# cpu.net
KiCad netlist of a schematic drawn in Altium Designer
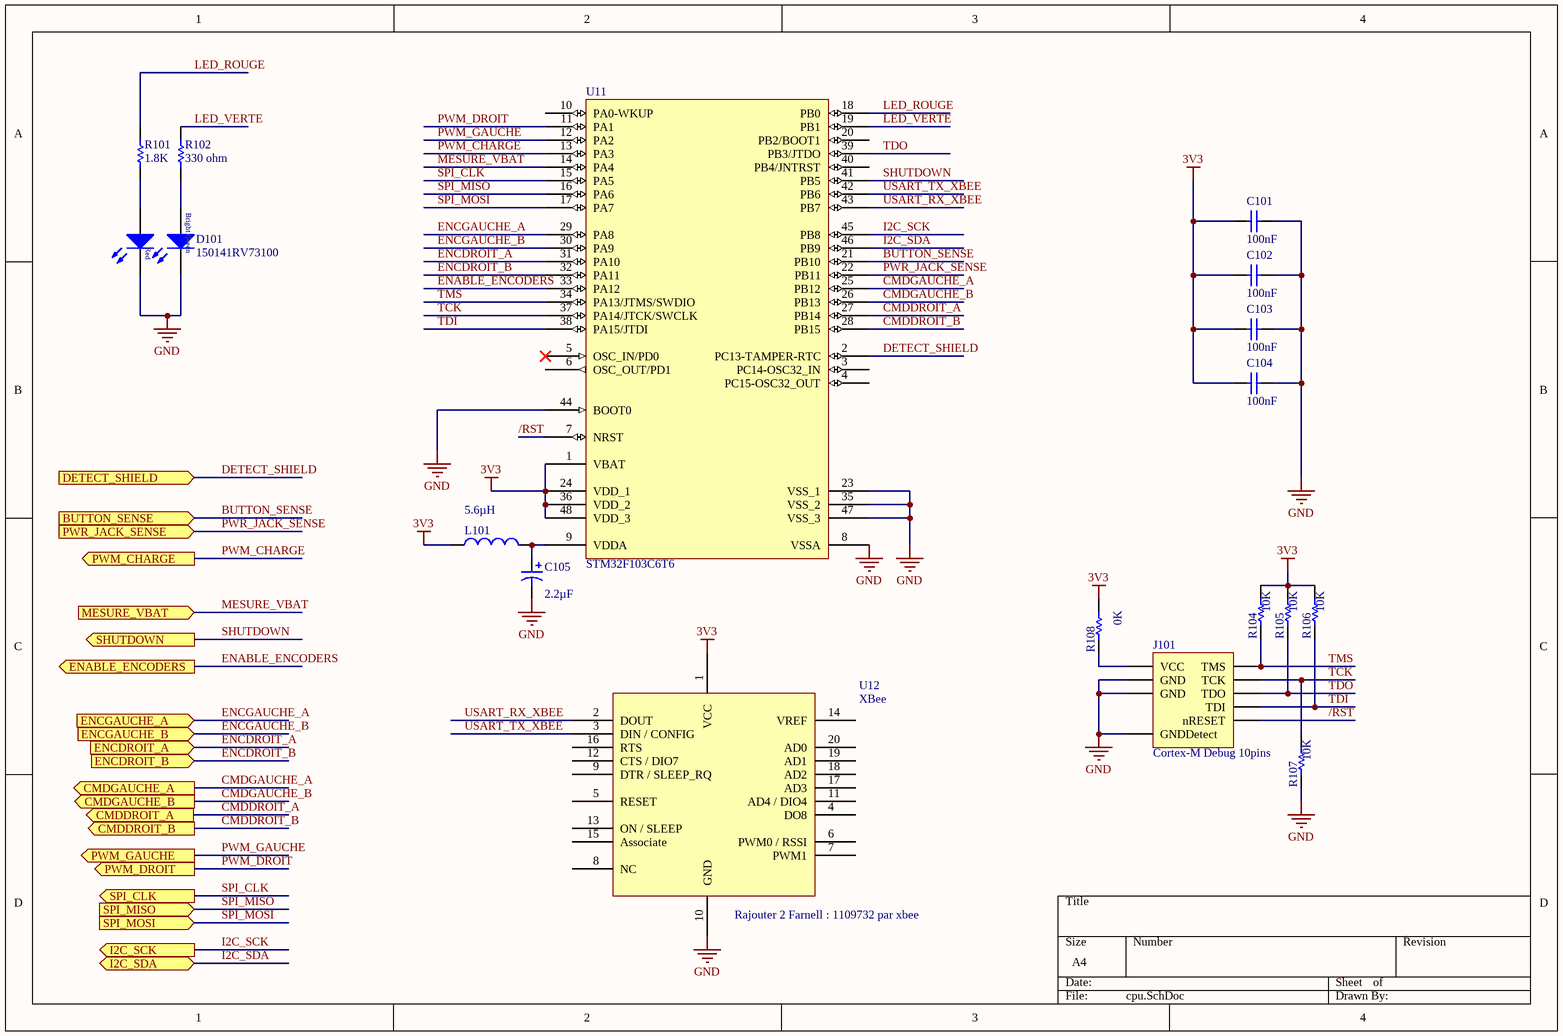
[diagram p0: cpu.SchDoc]

(export (version "E")
  (design (tool "Eeschema 10.0.6"))
  (components
    (comp (ref "C101")
      (value "100nF")
      (footprint "CAPC1206(3216)170_L")
      (description "CAP 100nF 50V ±10% 1206 (3216 Metric) Thickness 1.7mm SMD")
      (fields (field (name "TOLERANCE") "Â±10%") (field (name "Comment") "CAP 100nF"))
      (libsource (lib "Altium Content Vault") (part "CMP-1037-04201-1"))
    )
    (comp (ref "C102")
      (value "100nF")
      (footprint "CAPC1206(3216)170_L")
      (description "CAP 100nF 50V ±10% 1206 (3216 Metric) Thickness 1.7mm SMD")
      (fields (field (name "TOLERANCE") "Â±10%") (field (name "Comment") "CAP 100nF"))
      (libsource (lib "Altium Content Vault") (part "CMP-1037-04201-1"))
    )
    (comp (ref "C103")
      (value "100nF")
      (footprint "CAPC1206(3216)170_L")
      (description "CAP 100nF 50V ±10% 1206 (3216 Metric) Thickness 1.7mm SMD")
      (fields (field (name "TOLERANCE") "Â±10%") (field (name "Comment") "CAP 100nF"))
      (libsource (lib "Altium Content Vault") (part "CMP-1037-04201-1"))
    )
    (comp (ref "C104")
      (value "100nF")
      (footprint "CAPC1206(3216)170_L")
      (description "CAP 100nF 50V ±10% 1206 (3216 Metric) Thickness 1.7mm SMD")
      (fields (field (name "TOLERANCE") "Â±10%") (field (name "Comment") "CAP 100nF"))
      (libsource (lib "Altium Content Vault") (part "CMP-1037-04201-1"))
    )
    (comp (ref "C105")
      (value "2.2µF")
      (footprint "B")
      (description "Solid Tantalum Chip Capacitor, Standard T491 Series - Industrial Grade")
      (fields (field (name "Comment") "T491B") (field (name "PUBLISHER") "Altium Limited"))
      (libsource (lib "KEMET Chip Capacitor") (part "T491B"))
    )
    (comp (ref "D101")
      (value "150141RV73100")
      (footprint "3528_A")
      (description "SMD Bi-Color Top LED, WL-SBTW, Red & Bright Green")
      (fields (field (name "MANUFACTURER") "Wuerth Elektronik"))
      (libsource (lib "Altium Content Vault") (part "CMP-1430-00001-1"))
    )
    (comp (ref "J101")
      (value "Cortex-M Debug 10pins")
      (footprint "Cortex M Debug")
      (libsource (lib "INSA") (part "Cortex-M Debug 10pins"))
    )
    (comp (ref "L101")
      (value "5.6µH")
      (footprint "1812")
      (description "Inductor SMD")
      (fields (field (name "Comment") "Inductor") (field (name "PUBLISHER") "Altium Limited"))
      (libsource (lib "INSA") (part "Inductor"))
    )
    (comp (ref "R101")
      (value "1.8K")
      (footprint "RESC0805(2012)_N")
      (description "1K8 0.125W 5% 0805 (2012 Metric)  SMD")
      (fields (field (name "POWER") "0.125 W") (field (name "TOLERANCE") "5 %"))
      (libsource (lib "Altium Content Vault") (part "CMP-1013-00080-1"))
    )
    (comp (ref "R102")
      (value "330 ohm")
      (footprint "RESC0805(2012)_L")
      (description "330R 0.125W 5% 0805 (2012 Metric)  SMD")
      (fields (field (name "TOLERANCE") "5 %") (field (name "POWER") "0.125 W"))
      (libsource (lib "Altium Content Vault") (part "CMP-1013-00062-1"))
    )
    (comp (ref "R104")
      (value "10K")
      (footprint "RESC1206(3216)_M")
      (description "10K 0.25W 5% 1206 (3216 Metric)  SMD")
      (fields (field (name "POWER") "0.25 W") (field (name "TOLERANCE") "5 %"))
      (libsource (lib "Altium Content Vault") (part "CMP-1014-00098-1"))
    )
    (comp (ref "R105")
      (value "10K")
      (footprint "RESC1206(3216)_M")
      (description "10K 0.25W 5% 1206 (3216 Metric)  SMD")
      (fields (field (name "POWER") "0.25 W") (field (name "TOLERANCE") "5 %"))
      (libsource (lib "Altium Content Vault") (part "CMP-1014-00098-1"))
    )
    (comp (ref "R106")
      (value "10K")
      (footprint "RESC1206(3216)_M")
      (description "10K 0.25W 5% 1206 (3216 Metric)  SMD")
      (fields (field (name "POWER") "0.25 W") (field (name "TOLERANCE") "5 %"))
      (libsource (lib "Altium Content Vault") (part "CMP-1014-00098-1"))
    )
    (comp (ref "R107")
      (value "10K")
      (footprint "RESC1206(3216)_M")
      (description "10K 0.25W 5% 1206 (3216 Metric)  SMD")
      (fields (field (name "POWER") "0.25 W") (field (name "TOLERANCE") "5 %"))
      (libsource (lib "Altium Content Vault") (part "CMP-1014-00098-1"))
    )
    (comp (ref "R108")
      (value "0K")
      (footprint "RESC1206(3216)_M")
      (description "10K 0.25W 5% 1206 (3216 Metric)  SMD")
      (fields (field (name "POWER") "0.25 W") (field (name "TOLERANCE") "5 %"))
      (libsource (lib "Altium Content Vault") (part "CMP-1014-00098-1"))
    )
    (comp (ref "U11")
      (value "STM32F103C6T6")
      (footprint "LQFP48_N")
      (description "STM32 ARM-based 32-bit MCU with 32 Kbytes Flash, 48-pin LQFP, Industrial Temperature")
      (fields (field (name "PUBLISHER") "Altium Limited"))
      (libsource (lib "ST Microcontroller 32-Bit STM32") (part "STM32F103C6T6"))
    )
    (comp (ref "U12")
      (value "XBee")
      (footprint "XBee")
      (description "Xbee RF transceiver from Digi")
      (libsource (lib "INSA") (part "XBee"))
    )
  )
  (nets
    (net (code "1") (name "/BUTTON_SENSE") (class "Default")
      (node (ref "U11") (pin "21") (pinfunction "PB10_21") (pintype "bidirectional"))
    )
    (net (code "2") (name "/CMDDROIT_A") (class "Default")
      (node (ref "U11") (pin "27") (pinfunction "PB14_27") (pintype "bidirectional"))
    )
    (net (code "3") (name "/CMDDROIT_B") (class "Default")
      (node (ref "U11") (pin "28") (pinfunction "PB15_28") (pintype "bidirectional"))
    )
    (net (code "4") (name "/CMDGAUCHE_A") (class "Default")
      (node (ref "U11") (pin "25") (pinfunction "PB12_25") (pintype "bidirectional"))
    )
    (net (code "5") (name "/CMDGAUCHE_B") (class "Default")
      (node (ref "U11") (pin "26") (pinfunction "PB13_26") (pintype "bidirectional"))
    )
    (net (code "6") (name "/DETECT_SHIELD") (class "Default")
      (node (ref "U11") (pin "2") (pinfunction "PC13-TAMPER-RTC_2") (pintype "bidirectional"))
    )
    (net (code "7") (name "/ENABLE_ENCODERS") (class "Default")
      (node (ref "U11") (pin "33") (pinfunction "PA12_33") (pintype "bidirectional"))
    )
    (net (code "8") (name "/ENCDROIT_A") (class "Default")
      (node (ref "U11") (pin "31") (pinfunction "PA10_31") (pintype "bidirectional"))
    )
    (net (code "9") (name "/ENCDROIT_B") (class "Default")
      (node (ref "U11") (pin "32") (pinfunction "PA11_32") (pintype "bidirectional"))
    )
    (net (code "10") (name "/ENCGAUCHE_A") (class "Default")
      (node (ref "U11") (pin "29") (pinfunction "PA8_29") (pintype "bidirectional"))
    )
    (net (code "11") (name "/ENCGAUCHE_B") (class "Default")
      (node (ref "U11") (pin "30") (pinfunction "PA9_30") (pintype "bidirectional"))
    )
    (net (code "12") (name "/I2C_SCK") (class "Default")
      (node (ref "U11") (pin "45") (pinfunction "PB8_45") (pintype "bidirectional"))
    )
    (net (code "13") (name "/I2C_SDA") (class "Default")
      (node (ref "U11") (pin "46") (pinfunction "PB9_46") (pintype "bidirectional"))
    )
    (net (code "14") (name "/LED_ROUGE") (class "Default")
      (node (ref "R101") (pin "2") (pinfunction "2_2") (pintype "passive"))
      (node (ref "U11") (pin "18") (pinfunction "PB0_18") (pintype "bidirectional"))
    )
    (net (code "15") (name "/LED_VERTE") (class "Default")
      (node (ref "R102") (pin "2") (pinfunction "2_2") (pintype "passive"))
      (node (ref "U11") (pin "19") (pinfunction "PB1_19") (pintype "bidirectional"))
    )
    (net (code "16") (name "/MESURE_VBAT") (class "Default")
      (node (ref "U11") (pin "14") (pinfunction "PA4_14") (pintype "bidirectional"))
    )
    (net (code "17") (name "/PWM_CHARGE") (class "Default")
      (node (ref "U11") (pin "13") (pinfunction "PA3_13") (pintype "bidirectional"))
    )
    (net (code "18") (name "/PWM_DROIT") (class "Default")
      (node (ref "U11") (pin "11") (pinfunction "PA1_11") (pintype "bidirectional"))
    )
    (net (code "19") (name "/PWM_GAUCHE") (class "Default")
      (node (ref "U11") (pin "12") (pinfunction "PA2_12") (pintype "bidirectional"))
    )
    (net (code "20") (name "/PWR_JACK_SENSE") (class "Default")
      (node (ref "U11") (pin "22") (pinfunction "PB11_22") (pintype "bidirectional"))
    )
    (net (code "21") (name "/SHUTDOWN") (class "Default")
      (node (ref "U11") (pin "41") (pinfunction "PB5_41") (pintype "bidirectional"))
    )
    (net (code "22") (name "/SPI_CLK") (class "Default")
      (node (ref "U11") (pin "15") (pinfunction "PA5_15") (pintype "bidirectional"))
    )
    (net (code "23") (name "/SPI_MISO") (class "Default")
      (node (ref "U11") (pin "16") (pinfunction "PA6_16") (pintype "bidirectional"))
    )
    (net (code "24") (name "/SPI_MOSI") (class "Default")
      (node (ref "U11") (pin "17") (pinfunction "PA7_17") (pintype "bidirectional"))
    )
    (net (code "25") (name "/TCK") (class "Default")
      (node (ref "J101") (pin "4") (pinfunction "TCK_4") (pintype "passive"))
      (node (ref "R107") (pin "2") (pinfunction "2_2") (pintype "passive"))
      (node (ref "U11") (pin "37") (pinfunction "PA14/JTCK/SWCLK_37") (pintype "bidirectional"))
    )
    (net (code "26") (name "/TDI") (class "Default")
      (node (ref "J101") (pin "8") (pinfunction "TDI_8") (pintype "passive"))
      (node (ref "R106") (pin "1") (pinfunction "1_1") (pintype "passive"))
      (node (ref "U11") (pin "38") (pinfunction "PA15/JTDI_38") (pintype "bidirectional"))
    )
    (net (code "27") (name "/TDO") (class "Default")
      (node (ref "J101") (pin "6") (pinfunction "TDO_6") (pintype "passive"))
      (node (ref "R105") (pin "1") (pinfunction "1_1") (pintype "passive"))
      (node (ref "U11") (pin "39") (pinfunction "PB3/JTDO_39") (pintype "bidirectional"))
    )
    (net (code "28") (name "/TMS") (class "Default")
      (node (ref "J101") (pin "2") (pinfunction "TMS_2") (pintype "passive"))
      (node (ref "R104") (pin "1") (pinfunction "1_1") (pintype "passive"))
      (node (ref "U11") (pin "34") (pinfunction "PA13/JTMS/SWDIO_34") (pintype "bidirectional"))
    )
    (net (code "29") (name "/USART_RX_XBEE") (class "Default")
      (node (ref "U11") (pin "43") (pinfunction "PB7_43") (pintype "bidirectional"))
      (node (ref "U12") (pin "2") (pinfunction "DOUT_2") (pintype "passive"))
    )
    (net (code "30") (name "/USART_TX_XBEE") (class "Default")
      (node (ref "U11") (pin "42") (pinfunction "PB6_42") (pintype "bidirectional"))
      (node (ref "U12") (pin "3") (pinfunction "DIN_/_CONFIG_3") (pintype "passive"))
    )
    (net (code "31") (name "/{slash}RST") (class "Default")
      (node (ref "J101") (pin "10") (pinfunction "nRESET_10") (pintype "passive"))
      (node (ref "U11") (pin "7") (pinfunction "NRST_7") (pintype "bidirectional"))
    )
    (net (code "32") (name "3V3") (class "Default")
      (node (ref "C101") (pin "2") (pinfunction "2_2") (pintype "passive"))
      (node (ref "C102") (pin "2") (pinfunction "2_2") (pintype "passive"))
      (node (ref "C103") (pin "2") (pinfunction "2_2") (pintype "passive"))
      (node (ref "C104") (pin "2") (pinfunction "2_2") (pintype "passive"))
      (node (ref "L101") (pin "1") (pinfunction "1_1") (pintype "passive"))
      (node (ref "R104") (pin "2") (pinfunction "2_2") (pintype "passive"))
      (node (ref "R105") (pin "2") (pinfunction "2_2") (pintype "passive"))
      (node (ref "R106") (pin "2") (pinfunction "2_2") (pintype "passive"))
      (node (ref "R108") (pin "2") (pinfunction "2_2") (pintype "passive"))
      (node (ref "U11") (pin "1") (pinfunction "VBAT_1") (pintype "power_in"))
      (node (ref "U11") (pin "24") (pinfunction "VDD_1_24") (pintype "power_in"))
      (node (ref "U11") (pin "36") (pinfunction "VDD_2_36") (pintype "power_in"))
      (node (ref "U11") (pin "48") (pinfunction "VDD_3_48") (pintype "power_in"))
      (node (ref "U12") (pin "1") (pinfunction "VCC_1") (pintype "passive"))
    )
    (net (code "33") (name "GND") (class "Default")
      (node (ref "C101") (pin "1") (pinfunction "1_1") (pintype "passive"))
      (node (ref "C102") (pin "1") (pinfunction "1_1") (pintype "passive"))
      (node (ref "C103") (pin "1") (pinfunction "1_1") (pintype "passive"))
      (node (ref "C104") (pin "1") (pinfunction "1_1") (pintype "passive"))
      (node (ref "C105") (pin "2") (pinfunction "2_2") (pintype "passive"))
      (node (ref "D101") (pin "3") (pinfunction "C_3") (pintype "passive"))
      (node (ref "D101") (pin "4") (pinfunction "C_4") (pintype "passive"))
      (node (ref "J101") (pin "3") (pinfunction "GND_3") (pintype "passive"))
      (node (ref "J101") (pin "5") (pinfunction "GND_5") (pintype "passive"))
      (node (ref "J101") (pin "9") (pinfunction "GNDDetect_9") (pintype "passive"))
      (node (ref "R107") (pin "1") (pinfunction "1_1") (pintype "passive"))
      (node (ref "U11") (pin "23") (pinfunction "VSS_1_23") (pintype "power_in"))
      (node (ref "U11") (pin "35") (pinfunction "VSS_2_35") (pintype "power_in"))
      (node (ref "U11") (pin "44") (pinfunction "BOOT0_44") (pintype "input"))
      (node (ref "U11") (pin "47") (pinfunction "VSS_3_47") (pintype "power_in"))
      (node (ref "U11") (pin "8") (pinfunction "VSSA_8") (pintype "power_in"))
      (node (ref "U12") (pin "10") (pinfunction "GND_10") (pintype "passive"))
    )
    (net (code "34") (name "Net-(D101-A-Pad1)") (class "Default")
      (node (ref "D101") (pin "1") (pinfunction "A_1") (pintype "passive"))
      (node (ref "R101") (pin "1") (pinfunction "1_1") (pintype "passive"))
    )
    (net (code "35") (name "Net-(D101-A-Pad2)") (class "Default")
      (node (ref "D101") (pin "2") (pinfunction "A_2") (pintype "passive"))
      (node (ref "R102") (pin "1") (pinfunction "1_1") (pintype "passive"))
    )
    (net (code "36") (name "Net-(J101-VCC)") (class "Default")
      (node (ref "J101") (pin "1") (pinfunction "VCC_1") (pintype "passive"))
      (node (ref "R108") (pin "1") (pinfunction "1_1") (pintype "passive"))
    )
    (net (code "37") (name "Net-(U11-VDDA)") (class "Default")
      (node (ref "C105") (pin "1") (pinfunction "1_1") (pintype "passive"))
      (node (ref "L101") (pin "2") (pinfunction "2_2") (pintype "passive"))
      (node (ref "U11") (pin "9") (pinfunction "VDDA_9") (pintype "power_in"))
    )
    (net (code "38") (name "unconnected-(U11-OSC_IN{slash}PD0-Pad5)") (class "Default")
      (node (ref "U11") (pin "5") (pinfunction "OSC_IN/PD0_5") (pintype "input+no_connect"))
    )
    (net (code "39") (name "unconnected-(U11-OSC_OUT{slash}PD1-Pad6)") (class "Default")
      (node (ref "U11") (pin "6") (pinfunction "OSC_OUT/PD1_6") (pintype "output"))
    )
    (net (code "40") (name "unconnected-(U11-PA0-WKUP-Pad10)") (class "Default")
      (node (ref "U11") (pin "10") (pinfunction "PA0-WKUP_10") (pintype "bidirectional"))
    )
    (net (code "41") (name "unconnected-(U11-PB2{slash}BOOT1-Pad20)") (class "Default")
      (node (ref "U11") (pin "20") (pinfunction "PB2/BOOT1_20") (pintype "bidirectional"))
    )
    (net (code "42") (name "unconnected-(U11-PB4{slash}JNTRST-Pad40)") (class "Default")
      (node (ref "U11") (pin "40") (pinfunction "PB4/JNTRST_40") (pintype "bidirectional"))
    )
    (net (code "43") (name "unconnected-(U11-PC14-OSC32_IN-Pad3)") (class "Default")
      (node (ref "U11") (pin "3") (pinfunction "PC14-OSC32_IN_3") (pintype "bidirectional"))
    )
    (net (code "44") (name "unconnected-(U11-PC15-OSC32_OUT-Pad4)") (class "Default")
      (node (ref "U11") (pin "4") (pinfunction "PC15-OSC32_OUT_4") (pintype "bidirectional"))
    )
    (net (code "45") (name "unconnected-(U12-AD0-Pad20)") (class "Default")
      (node (ref "U12") (pin "20") (pinfunction "AD0_20") (pintype "passive"))
    )
    (net (code "46") (name "unconnected-(U12-AD1-Pad19)") (class "Default")
      (node (ref "U12") (pin "19") (pinfunction "AD1_19") (pintype "passive"))
    )
    (net (code "47") (name "unconnected-(U12-AD2-Pad18)") (class "Default")
      (node (ref "U12") (pin "18") (pinfunction "AD2_18") (pintype "passive"))
    )
    (net (code "48") (name "unconnected-(U12-AD3-Pad17)") (class "Default")
      (node (ref "U12") (pin "17") (pinfunction "AD3_17") (pintype "passive"))
    )
    (net (code "49") (name "unconnected-(U12-AD4_{slash}_DIO4-Pad11)") (class "Default")
      (node (ref "U12") (pin "11") (pinfunction "AD4_/_DIO4_11") (pintype "passive"))
    )
    (net (code "50") (name "unconnected-(U12-Associate-Pad15)") (class "Default")
      (node (ref "U12") (pin "15") (pinfunction "Associate_15") (pintype "passive"))
    )
    (net (code "51") (name "unconnected-(U12-CTS_{slash}_DIO7-Pad12)") (class "Default")
      (node (ref "U12") (pin "12") (pinfunction "CTS_/_DIO7_12") (pintype "passive"))
    )
    (net (code "52") (name "unconnected-(U12-DO8-Pad4)") (class "Default")
      (node (ref "U12") (pin "4") (pinfunction "DO8_4") (pintype "passive"))
    )
    (net (code "53") (name "unconnected-(U12-DTR_{slash}_SLEEP_RQ-Pad9)") (class "Default")
      (node (ref "U12") (pin "9") (pinfunction "DTR_/_SLEEP_RQ_9") (pintype "passive"))
    )
    (net (code "54") (name "unconnected-(U12-NC-Pad8)") (class "Default")
      (node (ref "U12") (pin "8") (pinfunction "NC_8") (pintype "passive"))
    )
    (net (code "55") (name "unconnected-(U12-ON_{slash}_SLEEP-Pad13)") (class "Default")
      (node (ref "U12") (pin "13") (pinfunction "ON_/_SLEEP_13") (pintype "passive"))
    )
    (net (code "56") (name "unconnected-(U12-PWM0_{slash}_RSSI-Pad6)") (class "Default")
      (node (ref "U12") (pin "6") (pinfunction "PWM0_/_RSSI_6") (pintype "passive"))
    )
    (net (code "57") (name "unconnected-(U12-PWM1-Pad7)") (class "Default")
      (node (ref "U12") (pin "7") (pinfunction "PWM1_7") (pintype "passive"))
    )
    (net (code "58") (name "unconnected-(U12-RESET-Pad5)") (class "Default")
      (node (ref "U12") (pin "5") (pinfunction "RESET_5") (pintype "passive"))
    )
    (net (code "59") (name "unconnected-(U12-RTS-Pad16)") (class "Default")
      (node (ref "U12") (pin "16") (pinfunction "RTS_16") (pintype "passive"))
    )
    (net (code "60") (name "unconnected-(U12-VREF-Pad14)") (class "Default")
      (node (ref "U12") (pin "14") (pinfunction "VREF_14") (pintype "passive"))
    )
  )
)
